# Multiplexers.net
KiCad netlist of a schematic drawn in Altium Designer
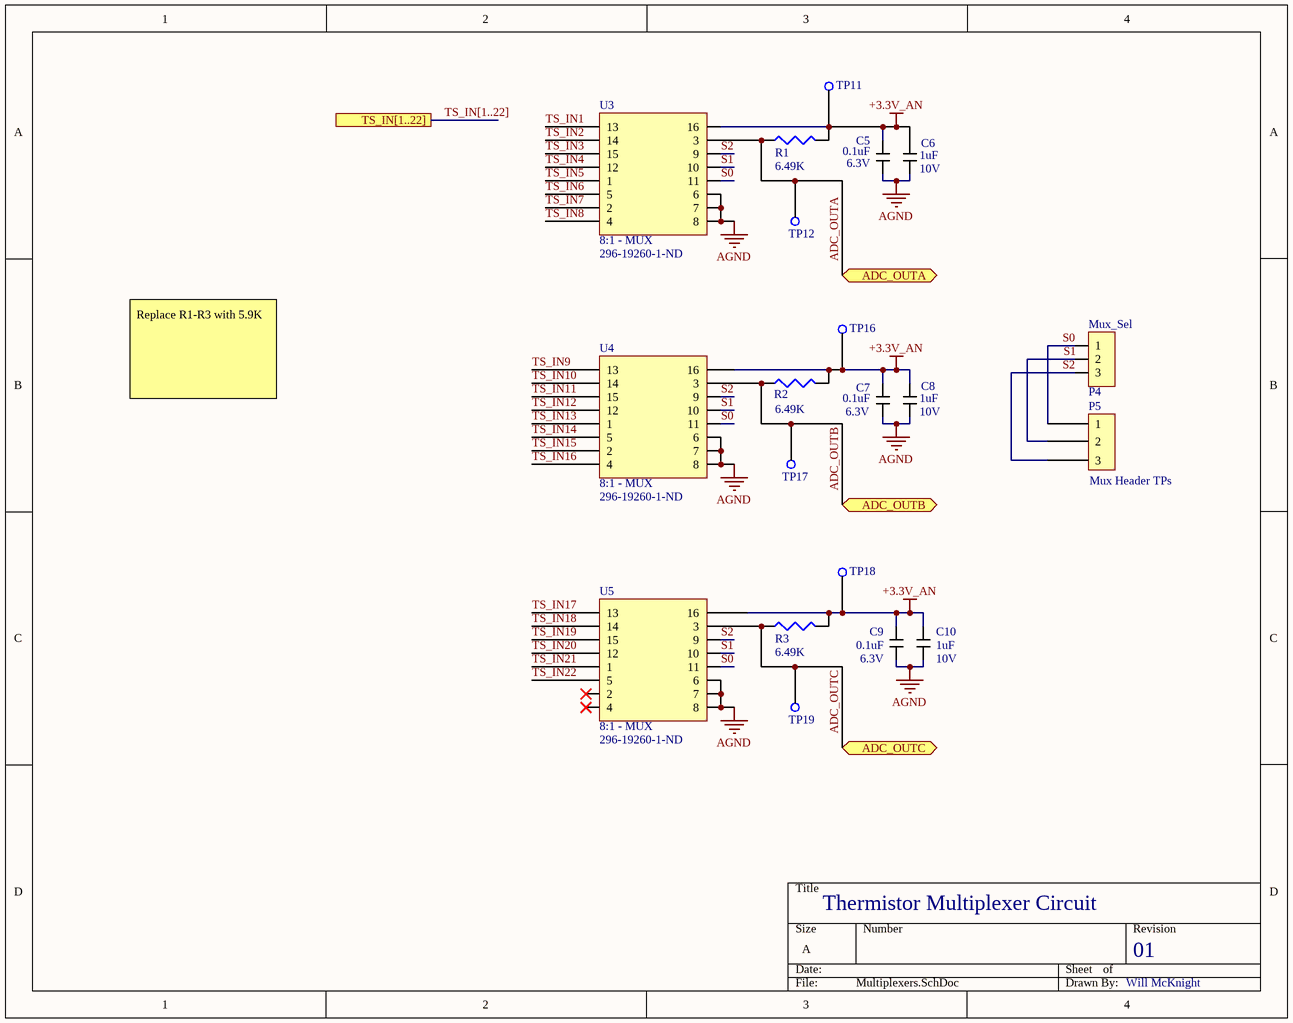
[diagram p0: Multiplexers.SchDoc]

(export (version "E")
  (design (tool "Eeschema 10.0.6"))
  (components
    (comp (ref "C5")
      (value "0.1uF")
      (footprint "0.1uF Bypass Capacitor")
      (description "0.1uF Bypass Cap")
      (fields
        (field (name "MANUFACTURER") "KEMET")
        (field (name "MANUFACTURER PART NUMBER") "C0603C104K9RACTU")
        (field (name "VOLTAGE RATING") "6.3V")
      )
      (libsource (lib "Schematic_Library") (part "0.1uF Cap"))
    )
    (comp (ref "C6")
      (value "1uF")
      (footprint "PCB_Librayr:1uf_Samsung")
      (description "1uF Samsung Cap")
      (fields
        (field (name "MANUFACTURER") "Samsung")
        (field (name "MANUFACTURER PART NUMBER") "CL10B105KP8NNNC")
        (field (name "CAPACITANCE") "1uF")
        (field (name "VOLTAGE RATING") "10V")
      )
      (libsource (lib "Schematic_Library") (part "1uF Samsung Cap"))
    )
    (comp (ref "C7")
      (value "0.1uF")
      (footprint "0.1uF Bypass Capacitor")
      (description "0.1uF Bypass Cap")
      (fields
        (field (name "MANUFACTURER") "KEMET")
        (field (name "MANUFACTURER PART NUMBER") "C0603C104K9RACTU")
        (field (name "VOLTAGE RATING") "6.3V")
      )
      (libsource (lib "Schematic_Library") (part "0.1uF Cap"))
    )
    (comp (ref "C8")
      (value "1uF")
      (footprint "PCB_Librayr:1uf_Samsung")
      (description "1uF Samsung Cap")
      (fields
        (field (name "MANUFACTURER") "Samsung")
        (field (name "MANUFACTURER PART NUMBER") "CL10B105KP8NNNC")
        (field (name "CAPACITANCE") "1uF")
      )
      (libsource (lib "Schematic_Library") (part "1uF Samsung Cap"))
    )
    (comp (ref "C9")
      (value "0.1uF")
      (footprint "0.1uF Bypass Capacitor")
      (description "0.1uF Bypass Cap")
      (fields
        (field (name "MANUFACTURER") "KEMET")
        (field (name "MANUFACTURER PART NUMBER") "C0603C104K9RACTU")
        (field (name "VOLTAGE RATING") "6.3V")
      )
      (libsource (lib "Schematic_Library") (part "0.1uF Cap"))
    )
    (comp (ref "C10")
      (value "1uF")
      (footprint "PCB_Librayr:1uf_Samsung")
      (description "1uF Samsung Cap")
      (fields
        (field (name "MANUFACTURER") "Samsung")
        (field (name "MANUFACTURER PART NUMBER") "CL10B105KP8NNNC")
        (field (name "CAPACITANCE") "1uF")
        (field (name "VOLTAGE RATING") "10V")
      )
      (libsource (lib "Schematic_Library") (part "1uF Samsung Cap"))
    )
    (comp (ref "P4")
      (value "Mux_Sel")
      (footprint "3-Screw-terminal-Mux-Select")
      (description "Mux Select")
      (fields
        (field (name "MANUFACTURER") "Wurth Electronics")
        (field (name "MANUFACTURER PART NUMBER") "691103110003")
      )
      (libsource (lib "Schematic_Library") (part "3-Screw-Terminal-Mux-Select"))
    )
    (comp (ref "P5")
      (value "3 POS Mux Select Header")
      (footprint "Mux Select 3 Pos Header Pin")
      (description "Mux Sel Header TP")
      (fields
        (field (name "MANUFACTURER") "Adam Equipment")
        (field (name "MANUFACTURER PART NUMBER") "PH1RA-03-UA")
      )
      (libsource (lib "Schematic_Library") (part "3 POS Mux Select Header"))
    )
    (comp (ref "R1")
      (value "6.49kOhm SMD Resistor")
      (footprint "RESC2012X06N")
      (fields
        (field (name "MANUFACTURER") "Panasonic")
        (field (name "MANUFACTURER PART NUMBER") "ERA6AEB6491V")
        (field (name "TOLERANCE") "0.1%")
        (field (name "RESISTANCE") "6.49K")
      )
      (libsource (lib "Schematic_Library") (part "6.49kOhm SMD Resistor"))
    )
    (comp (ref "R2")
      (value "6.49kOhm SMD Resistor")
      (footprint "RESC2012X06N")
      (fields
        (field (name "MANUFACTURER") "Panasonic")
        (field (name "MANUFACTURER PART NUMBER") "ERA6AEB6491V")
        (field (name "TOLERANCE") "0.1%")
        (field (name "RESISTANCE") "6.49K")
      )
      (libsource (lib "Schematic_Library") (part "6.49kOhm SMD Resistor"))
    )
    (comp (ref "R3")
      (value "6.49kOhm SMD Resistor")
      (footprint "RESC2012X06N")
      (fields
        (field (name "MANUFACTURER") "Panasonic")
        (field (name "MANUFACTURER PART NUMBER") "ERA6AEB6491V")
        (field (name "TOLERANCE") "0.1%")
        (field (name "RESISTANCE") "6.49K")
      )
      (libsource (lib "Schematic_Library") (part "6.49kOhm SMD Resistor"))
    )
    (comp (ref "TP11")
      (value "Test Point")
      (footprint "Test Point")
      (libsource (lib "Schematic_Library") (part "Test Point"))
    )
    (comp (ref "TP12")
      (value "Test Point")
      (footprint "Test Point")
      (libsource (lib "Schematic_Library") (part "Test Point"))
    )
    (comp (ref "TP16")
      (value "Test Point")
      (footprint "Test Point")
      (libsource (lib "Schematic_Library") (part "Test Point"))
    )
    (comp (ref "TP17")
      (value "Test Point")
      (footprint "Test Point")
      (libsource (lib "Schematic_Library") (part "Test Point"))
    )
    (comp (ref "TP18")
      (value "Test Point")
      (footprint "Test Point")
      (libsource (lib "Schematic_Library") (part "Test Point"))
    )
    (comp (ref "TP19")
      (value "Test Point")
      (footprint "Test Point")
      (libsource (lib "Schematic_Library") (part "Test Point"))
    )
    (comp (ref "U3")
      (value "8:1 - MUX")
      (footprint "SOP127P600X175")
      (fields
        (field (name "MANUFACTURER") "Texas Instruments")
        (field (name "MANUFACTURER PART NUMBER") "SN74LV4051ATPWRQ1")
        (field (name "SUPPLIER PART NUMBER 1") "296-19260-1-ND")
      )
      (libsource (lib "Schematic_Library") (part "8{colon}1 - MUX"))
    )
    (comp (ref "U4")
      (value "8:1 - MUX")
      (footprint "SOP127P600X175")
      (fields
        (field (name "MANUFACTURER") "Texas Instruments")
        (field (name "MANUFACTURER PART NUMBER") "SN74LV4051ATPWRQ1")
        (field (name "SUPPLIER PART NUMBER 1") "296-19260-1-ND")
      )
      (libsource (lib "Schematic_Library") (part "8{colon}1 - MUX"))
    )
    (comp (ref "U5")
      (value "8:1 - MUX")
      (footprint "SOP127P600X175")
      (fields
        (field (name "MANUFACTURER") "Texas Instruments")
        (field (name "MANUFACTURER PART NUMBER") "SN74LV4051ATPWRQ1")
        (field (name "SUPPLIER PART NUMBER 1") "296-19260-1-ND")
      )
      (libsource (lib "Schematic_Library") (part "8{colon}1 - MUX"))
    )
  )
  (nets
    (net (code "1") (name "+3.3V_AN") (class "Default")
      (node (ref "C10") (pin "2") (pinfunction "2_2") (pintype "passive"))
      (node (ref "C5") (pin "2") (pinfunction "2_2") (pintype "passive"))
      (node (ref "C6") (pin "2") (pinfunction "2_2") (pintype "passive"))
      (node (ref "C7") (pin "2") (pinfunction "2_2") (pintype "passive"))
      (node (ref "C8") (pin "2") (pinfunction "2_2") (pintype "passive"))
      (node (ref "C9") (pin "2") (pinfunction "2_2") (pintype "passive"))
      (node (ref "R1") (pin "2") (pinfunction "2_2") (pintype "passive"))
      (node (ref "R2") (pin "2") (pinfunction "2_2") (pintype "passive"))
      (node (ref "R3") (pin "2") (pinfunction "2_2") (pintype "passive"))
      (node (ref "TP11") (pin "1") (pinfunction "1_1") (pintype "passive"))
      (node (ref "TP16") (pin "1") (pinfunction "1_1") (pintype "passive"))
      (node (ref "TP18") (pin "1") (pinfunction "1_1") (pintype "passive"))
      (node (ref "U3") (pin "16") (pinfunction "16_16") (pintype "passive"))
      (node (ref "U4") (pin "16") (pinfunction "16_16") (pintype "passive"))
      (node (ref "U5") (pin "16") (pinfunction "16_16") (pintype "passive"))
    )
    (net (code "2") (name "/ADC_OUTA") (class "Default")
      (node (ref "R1") (pin "1") (pinfunction "1_1") (pintype "passive"))
      (node (ref "TP12") (pin "1") (pinfunction "1_1") (pintype "passive"))
      (node (ref "U3") (pin "3") (pinfunction "3_3") (pintype "passive"))
    )
    (net (code "3") (name "/ADC_OUTB") (class "Default")
      (node (ref "R2") (pin "1") (pinfunction "1_1") (pintype "passive"))
      (node (ref "TP17") (pin "1") (pinfunction "1_1") (pintype "passive"))
      (node (ref "U4") (pin "3") (pinfunction "3_3") (pintype "passive"))
    )
    (net (code "4") (name "/ADC_OUTC") (class "Default")
      (node (ref "R3") (pin "1") (pinfunction "1_1") (pintype "passive"))
      (node (ref "TP19") (pin "1") (pinfunction "1_1") (pintype "passive"))
      (node (ref "U5") (pin "3") (pinfunction "3_3") (pintype "passive"))
    )
    (net (code "5") (name "/S0") (class "Default")
      (node (ref "P4") (pin "1") (pinfunction "1_1") (pintype "passive"))
      (node (ref "P5") (pin "1") (pinfunction "1_1") (pintype "passive"))
      (node (ref "U3") (pin "11") (pinfunction "11_11") (pintype "passive"))
      (node (ref "U4") (pin "11") (pinfunction "11_11") (pintype "passive"))
      (node (ref "U5") (pin "11") (pinfunction "11_11") (pintype "passive"))
    )
    (net (code "6") (name "/S1") (class "Default")
      (node (ref "P4") (pin "2") (pinfunction "2_2") (pintype "passive"))
      (node (ref "P5") (pin "2") (pinfunction "2_2") (pintype "passive"))
      (node (ref "U3") (pin "10") (pinfunction "10_10") (pintype "passive"))
      (node (ref "U4") (pin "10") (pinfunction "10_10") (pintype "passive"))
      (node (ref "U5") (pin "10") (pinfunction "10_10") (pintype "passive"))
    )
    (net (code "7") (name "/S2") (class "Default")
      (node (ref "P4") (pin "3") (pinfunction "3_3") (pintype "passive"))
      (node (ref "P5") (pin "3") (pinfunction "3_3") (pintype "passive"))
      (node (ref "U3") (pin "9") (pinfunction "9_9") (pintype "passive"))
      (node (ref "U4") (pin "9") (pinfunction "9_9") (pintype "passive"))
      (node (ref "U5") (pin "9") (pinfunction "9_9") (pintype "passive"))
    )
    (net (code "8") (name "/TS_IN1") (class "Default")
      (node (ref "U3") (pin "13") (pinfunction "13_13") (pintype "passive"))
    )
    (net (code "9") (name "/TS_IN2") (class "Default")
      (node (ref "U3") (pin "14") (pinfunction "14_14") (pintype "passive"))
    )
    (net (code "10") (name "/TS_IN3") (class "Default")
      (node (ref "U3") (pin "15") (pinfunction "15_15") (pintype "passive"))
    )
    (net (code "11") (name "/TS_IN4") (class "Default")
      (node (ref "U3") (pin "12") (pinfunction "12_12") (pintype "passive"))
    )
    (net (code "12") (name "/TS_IN5") (class "Default")
      (node (ref "U3") (pin "1") (pinfunction "1_1") (pintype "passive"))
    )
    (net (code "13") (name "/TS_IN6") (class "Default")
      (node (ref "U3") (pin "5") (pinfunction "5_5") (pintype "passive"))
    )
    (net (code "14") (name "/TS_IN7") (class "Default")
      (node (ref "U3") (pin "2") (pinfunction "2_2") (pintype "passive"))
    )
    (net (code "15") (name "/TS_IN8") (class "Default")
      (node (ref "U3") (pin "4") (pinfunction "4_4") (pintype "passive"))
    )
    (net (code "16") (name "/TS_IN9") (class "Default")
      (node (ref "U4") (pin "13") (pinfunction "13_13") (pintype "passive"))
    )
    (net (code "17") (name "/TS_IN10") (class "Default")
      (node (ref "U4") (pin "14") (pinfunction "14_14") (pintype "passive"))
    )
    (net (code "18") (name "/TS_IN11") (class "Default")
      (node (ref "U4") (pin "15") (pinfunction "15_15") (pintype "passive"))
    )
    (net (code "19") (name "/TS_IN12") (class "Default")
      (node (ref "U4") (pin "12") (pinfunction "12_12") (pintype "passive"))
    )
    (net (code "20") (name "/TS_IN13") (class "Default")
      (node (ref "U4") (pin "1") (pinfunction "1_1") (pintype "passive"))
    )
    (net (code "21") (name "/TS_IN14") (class "Default")
      (node (ref "U4") (pin "5") (pinfunction "5_5") (pintype "passive"))
    )
    (net (code "22") (name "/TS_IN15") (class "Default")
      (node (ref "U4") (pin "2") (pinfunction "2_2") (pintype "passive"))
    )
    (net (code "23") (name "/TS_IN16") (class "Default")
      (node (ref "U4") (pin "4") (pinfunction "4_4") (pintype "passive"))
    )
    (net (code "24") (name "/TS_IN17") (class "Default")
      (node (ref "U5") (pin "13") (pinfunction "13_13") (pintype "passive"))
    )
    (net (code "25") (name "/TS_IN18") (class "Default")
      (node (ref "U5") (pin "14") (pinfunction "14_14") (pintype "passive"))
    )
    (net (code "26") (name "/TS_IN19") (class "Default")
      (node (ref "U5") (pin "15") (pinfunction "15_15") (pintype "passive"))
    )
    (net (code "27") (name "/TS_IN20") (class "Default")
      (node (ref "U5") (pin "12") (pinfunction "12_12") (pintype "passive"))
    )
    (net (code "28") (name "/TS_IN21") (class "Default")
      (node (ref "U5") (pin "1") (pinfunction "1_1") (pintype "passive"))
    )
    (net (code "29") (name "/TS_IN22") (class "Default")
      (node (ref "U5") (pin "5") (pinfunction "5_5") (pintype "passive"))
    )
    (net (code "31") (name "AGND") (class "Default")
      (node (ref "C10") (pin "1") (pinfunction "1_1") (pintype "passive"))
      (node (ref "C5") (pin "1") (pinfunction "1_1") (pintype "passive"))
      (node (ref "C6") (pin "1") (pinfunction "1_1") (pintype "passive"))
      (node (ref "C7") (pin "1") (pinfunction "1_1") (pintype "passive"))
      (node (ref "C8") (pin "1") (pinfunction "1_1") (pintype "passive"))
      (node (ref "C9") (pin "1") (pinfunction "1_1") (pintype "passive"))
      (node (ref "U3") (pin "6") (pinfunction "6_6") (pintype "passive"))
      (node (ref "U3") (pin "7") (pinfunction "7_7") (pintype "passive"))
      (node (ref "U3") (pin "8") (pinfunction "8_8") (pintype "passive"))
      (node (ref "U4") (pin "6") (pinfunction "6_6") (pintype "passive"))
      (node (ref "U4") (pin "7") (pinfunction "7_7") (pintype "passive"))
      (node (ref "U4") (pin "8") (pinfunction "8_8") (pintype "passive"))
      (node (ref "U5") (pin "6") (pinfunction "6_6") (pintype "passive"))
      (node (ref "U5") (pin "7") (pinfunction "7_7") (pintype "passive"))
      (node (ref "U5") (pin "8") (pinfunction "8_8") (pintype "passive"))
    )
    (net (code "32") (name "unconnected-(U5-Pad2)") (class "Default")
      (node (ref "U5") (pin "2") (pinfunction "2_2") (pintype "passive+no_connect"))
    )
    (net (code "33") (name "unconnected-(U5-Pad4)") (class "Default")
      (node (ref "U5") (pin "4") (pinfunction "4_4") (pintype "passive+no_connect"))
    )
  )
)
